# TC4056Charge.net
KiCad netlist of a schematic drawn in Altium Designer
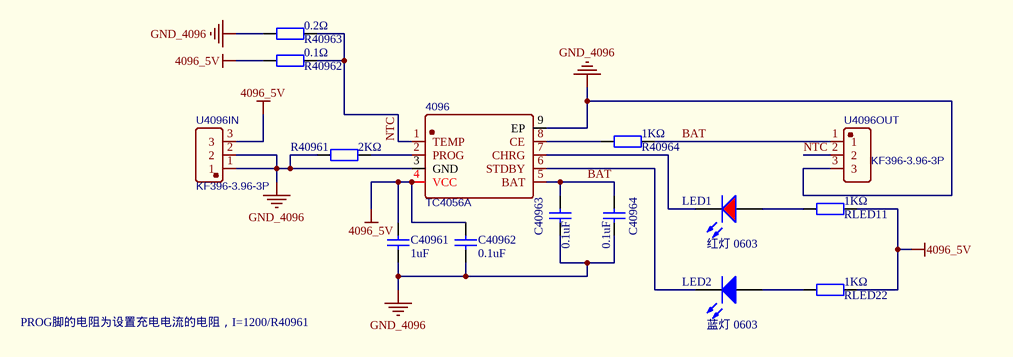
[diagram p0: TC4056Charge.SchDoc]

(export (version "E")
  (design (tool "Eeschema 10.0.6"))
  (components
    (comp (ref "4096")
      (value "TC4056A")
      (footprint "SOP-8_L4.9-W3.9-P1.27-LS6.0-BL-EP")
      (fields (field (name "BOM_SUPPLIER PART") "C84051"))
      (libsource (lib "ExportLIBCompile") (part "TC4056A"))
    )
    (comp (ref "C40961")
      (value "1uF")
      (footprint "1206_C")
      (description "贴片电容")
      (libsource (lib "AD封装2018.9.19Miscellaneous Devices LC") (part "1206 1uF (105) 10% 50V"))
    )
    (comp (ref "C40962")
      (value "0.1uF")
      (footprint "1206_C")
      (description "贴片电容")
      (libsource (lib "AD封装2018.9.19Miscellaneous Devices LC") (part "1206 1uF (105) 10% 50V"))
    )
    (comp (ref "C40963")
      (value "0.1uF")
      (footprint "1206_C")
      (description "贴片电容")
      (libsource (lib "AD封装2018.9.19Miscellaneous Devices LC") (part "1206 1uF (105) 10% 50V"))
    )
    (comp (ref "C40964")
      (value "0.1uF")
      (footprint "1206_C")
      (description "贴片电容")
      (libsource (lib "AD封装2018.9.19Miscellaneous Devices LC") (part "1206 1uF (105) 10% 50V"))
    )
    (comp (ref "LED1")
      (value "红灯 0603")
      (footprint "0603_LED_S1")
      (description "发光二极管")
      (libsource (lib "AD封装2018.9.19Miscellaneous Devices LC") (part "0603 红灯"))
    )
    (comp (ref "LED2")
      (value "蓝灯 0603")
      (footprint "0603_LED_S1")
      (description "发光二极管")
      (libsource (lib "AD封装2018.9.19Miscellaneous Devices LC") (part "0603 蓝灯"))
    )
    (comp (ref "R40961")
      (value "2KΩ")
      (footprint "1206_R")
      (description "贴片电阻")
      (libsource (lib "AD封装2018.9.19Miscellaneous Devices LC") (part "1206 0.1Ω (R100) 1%"))
    )
    (comp (ref "R40962")
      (value "0.1Ω")
      (footprint "1206_R")
      (description "贴片电阻")
      (libsource (lib "AD封装2018.9.19Miscellaneous Devices LC") (part "1206 0.1Ω (R100) 1%"))
    )
    (comp (ref "R40963")
      (value "0.2Ω")
      (footprint "1206_R")
      (description "贴片电阻")
      (libsource (lib "AD封装2018.9.19Miscellaneous Devices LC") (part "1206 0.1Ω (R100) 1%"))
    )
    (comp (ref "R40964")
      (value "1KΩ")
      (footprint "1206_R")
      (description "贴片电阻")
      (libsource (lib "AD封装2018.9.19Miscellaneous Devices LC") (part "1206 0.1Ω (R100) 1%"))
    )
    (comp (ref "RLED11")
      (value "1KΩ")
      (footprint "1206_R")
      (description "贴片电阻")
      (libsource (lib "AD封装2018.9.19Miscellaneous Devices LC") (part "1206 0.1Ω (R100) 1%"))
    )
    (comp (ref "RLED22")
      (value "1KΩ")
      (footprint "1206_R")
      (description "贴片电阻")
      (libsource (lib "AD封装2018.9.19Miscellaneous Devices LC") (part "1206 0.1Ω (R100) 1%"))
    )
    (comp (ref "U4096IN")
      (value "KF396-3.96-3P")
      (footprint "CONN-TH_3P-P3.96_KF396-3.96-3P")
      (fields (field (name "BOM_SUPPLIER PART") "C474895") (field (name "CONTRIBUTOR") "LCSC"))
      (libsource (lib "ExportLIBCompile") (part "KF396-3.96-3P"))
    )
    (comp (ref "U4096OUT")
      (value "KF396-3.96-3P")
      (footprint "CONN-TH_3P-P3.96_KF396-3.96-3P")
      (fields (field (name "BOM_SUPPLIER PART") "C474895") (field (name "CONTRIBUTOR") "LCSC"))
      (libsource (lib "ExportLIBCompile") (part "KF396-3.96-3P"))
    )
  )
  (nets
    (net (code "1") (name "/BAT") (class "Default")
      (node (ref "4096") (pin "5") (pinfunction "BAT_5") (pintype "passive"))
      (node (ref "C40963") (pin "2") (pinfunction "2_2") (pintype "passive"))
      (node (ref "C40964") (pin "2") (pinfunction "2_2") (pintype "passive"))
      (node (ref "R40964") (pin "2") (pinfunction "2_2") (pintype "passive"))
      (node (ref "U4096OUT") (pin "1") (pinfunction "1_1") (pintype "passive"))
    )
    (net (code "2") (name "/NTC") (class "Default")
      (node (ref "4096") (pin "1") (pinfunction "TEMP_1") (pintype "passive"))
      (node (ref "R40962") (pin "2") (pinfunction "2_2") (pintype "passive"))
      (node (ref "R40963") (pin "2") (pinfunction "2_2") (pintype "passive"))
      (node (ref "U4096OUT") (pin "2") (pinfunction "2_2") (pintype "passive"))
    )
    (net (code "3") (name "4096_5V") (class "Default")
      (node (ref "4096") (pin "4") (pinfunction "VCC_4") (pintype "passive"))
      (node (ref "C40961") (pin "2") (pinfunction "2_2") (pintype "passive"))
      (node (ref "C40962") (pin "2") (pinfunction "2_2") (pintype "passive"))
      (node (ref "R40962") (pin "1") (pinfunction "1_1") (pintype "passive"))
      (node (ref "RLED11") (pin "2") (pinfunction "2_2") (pintype "passive"))
      (node (ref "RLED22") (pin "2") (pinfunction "2_2") (pintype "passive"))
      (node (ref "U4096IN") (pin "3") (pinfunction "3_3") (pintype "passive"))
    )
    (net (code "4") (name "GND_4096") (class "Default")
      (node (ref "4096") (pin "3") (pinfunction "GND_3") (pintype "passive"))
      (node (ref "4096") (pin "9") (pinfunction "EP_9") (pintype "passive"))
      (node (ref "C40961") (pin "1") (pinfunction "1_1") (pintype "passive"))
      (node (ref "C40962") (pin "1") (pinfunction "1_1") (pintype "passive"))
      (node (ref "C40963") (pin "1") (pinfunction "1_1") (pintype "passive"))
      (node (ref "C40964") (pin "1") (pinfunction "1_1") (pintype "passive"))
      (node (ref "R40961") (pin "1") (pinfunction "1_1") (pintype "passive"))
      (node (ref "R40963") (pin "1") (pinfunction "1_1") (pintype "passive"))
      (node (ref "U4096IN") (pin "1") (pinfunction "1_1") (pintype "passive"))
      (node (ref "U4096IN") (pin "2") (pinfunction "2_2") (pintype "passive"))
      (node (ref "U4096OUT") (pin "3") (pinfunction "3_3") (pintype "passive"))
    )
    (net (code "5") (name "Net-(4096-CE)") (class "Default")
      (node (ref "4096") (pin "8") (pinfunction "CE_8") (pintype "passive"))
      (node (ref "R40964") (pin "1") (pinfunction "1_1") (pintype "passive"))
    )
    (net (code "6") (name "Net-(4096-CHRG)") (class "Default")
      (node (ref "4096") (pin "7") (pinfunction "CHRG_7") (pintype "passive"))
      (node (ref "LED1") (pin "K") (pinfunction "K_K") (pintype "passive"))
    )
    (net (code "7") (name "Net-(4096-PROG)") (class "Default")
      (node (ref "4096") (pin "2") (pinfunction "PROG_2") (pintype "passive"))
      (node (ref "R40961") (pin "2") (pinfunction "2_2") (pintype "passive"))
    )
    (net (code "8") (name "Net-(4096-STDBY)") (class "Default")
      (node (ref "4096") (pin "6") (pinfunction "STDBY_6") (pintype "passive"))
      (node (ref "LED2") (pin "K") (pinfunction "K_K") (pintype "passive"))
    )
    (net (code "9") (name "Net-(LED1-PadA)") (class "Default")
      (node (ref "LED1") (pin "A") (pinfunction "A_A") (pintype "passive"))
      (node (ref "RLED11") (pin "1") (pinfunction "1_1") (pintype "passive"))
    )
    (net (code "10") (name "Net-(LED2-PadA)") (class "Default")
      (node (ref "LED2") (pin "A") (pinfunction "A_A") (pintype "passive"))
      (node (ref "RLED22") (pin "1") (pinfunction "1_1") (pintype "passive"))
    )
  )
)
